# UC-520.net
KiCad netlist of a schematic drawn in Altium Designer
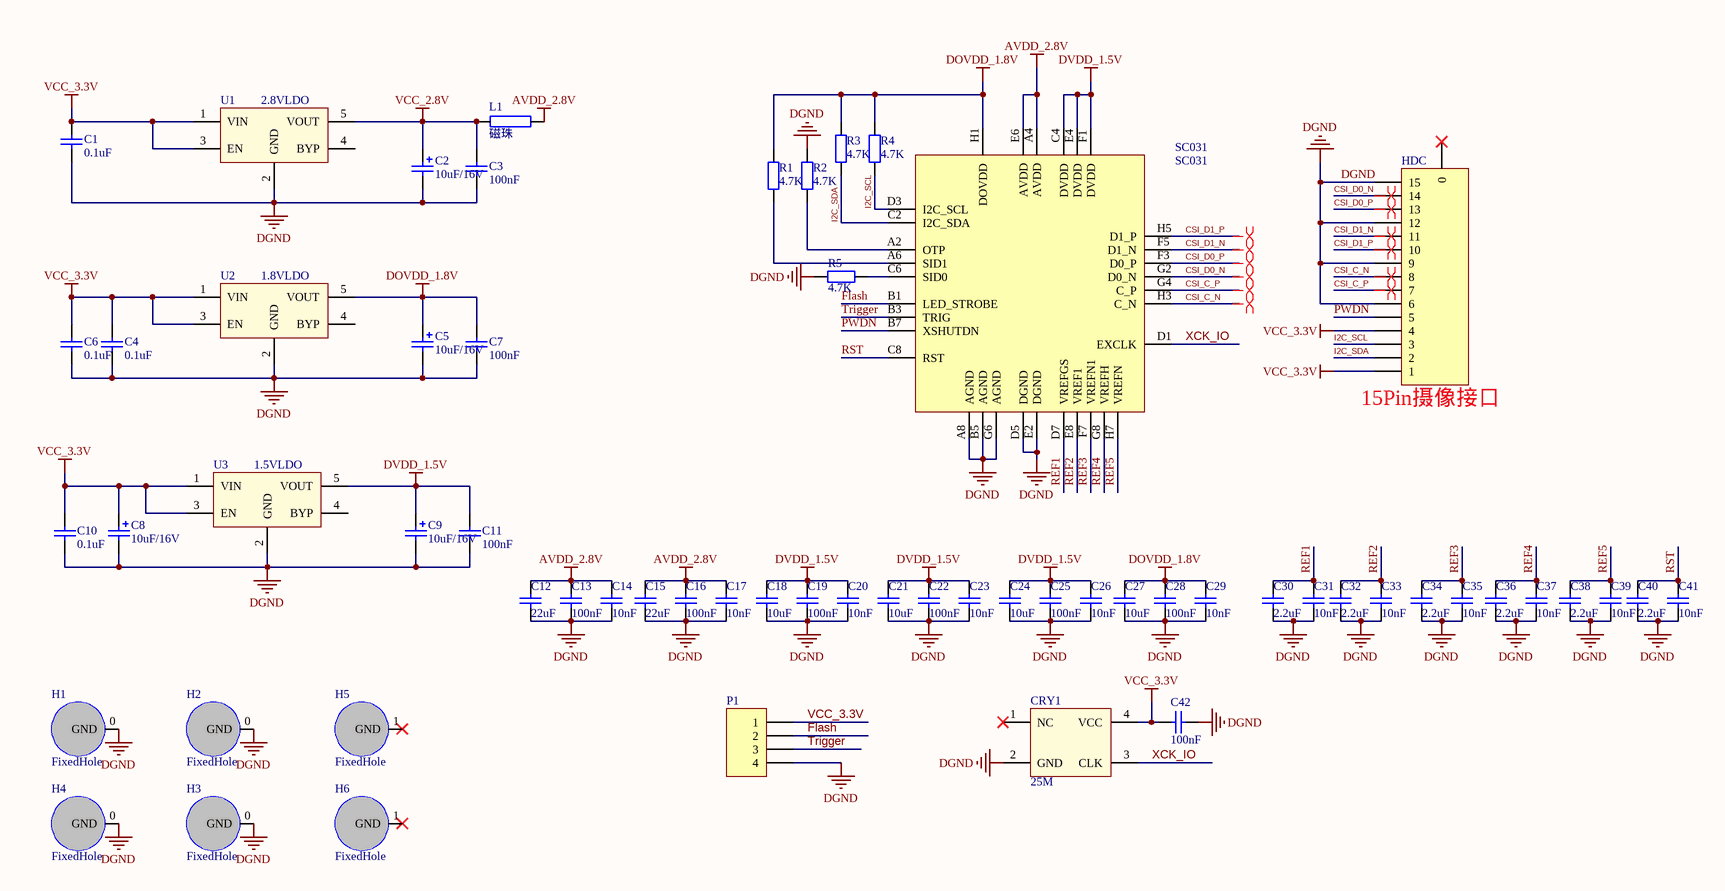
[diagram p0: UC-520.SchDoc]

(export (version "E")
  (design (tool "Eeschema 10.0.6"))
  (components
    (comp (ref "C1")
      (value "0.1uF")
      (footprint "C0603")
      (description "Capacitor")
      (fields (field (name "PUBLISHER") "Altium Limited"))
      (libsource (lib "Miscellaneous Devices") (part "Cap"))
    )
    (comp (ref "C2")
      (value "10uF/16V")
      (footprint "钽电容（A型）")
      (description "Polarized Capacitor (Axial)")
      (fields (field (name "PUBLISHER") "Altium Limited"))
      (libsource (lib "Miscellaneous Devices") (part "Cap Pol2"))
    )
    (comp (ref "C3")
      (value "100nF")
      (footprint "C0603")
      (description "Capacitor")
      (fields (field (name "PUBLISHER") "Altium Limited"))
      (libsource (lib "Miscellaneous Devices") (part "Cap"))
    )
    (comp (ref "C4")
      (value "0.1uF")
      (footprint "C0603")
      (description "Capacitor")
      (fields (field (name "PUBLISHER") "Altium Limited"))
      (libsource (lib "Miscellaneous Devices") (part "Cap"))
    )
    (comp (ref "C5")
      (value "10uF/16V")
      (footprint "钽电容（A型）")
      (description "Polarized Capacitor (Axial)")
      (fields (field (name "PUBLISHER") "Altium Limited"))
      (libsource (lib "Miscellaneous Devices") (part "Cap Pol2"))
    )
    (comp (ref "C6")
      (value "0.1uF")
      (footprint "C0603")
      (description "Capacitor")
      (fields (field (name "PUBLISHER") "Altium Limited"))
      (libsource (lib "Miscellaneous Devices") (part "Cap"))
    )
    (comp (ref "C7")
      (value "100nF")
      (footprint "C0603")
      (description "Capacitor")
      (fields (field (name "PUBLISHER") "Altium Limited"))
      (libsource (lib "Miscellaneous Devices") (part "Cap"))
    )
    (comp (ref "C8")
      (value "10uF/16V")
      (footprint "钽电容（A型）")
      (description "Polarized Capacitor (Axial)")
      (fields (field (name "PUBLISHER") "Altium Limited"))
      (libsource (lib "Miscellaneous Devices") (part "Cap Pol2"))
    )
    (comp (ref "C9")
      (value "10uF/16V")
      (footprint "钽电容（A型）")
      (description "Polarized Capacitor (Axial)")
      (fields (field (name "PUBLISHER") "Altium Limited"))
      (libsource (lib "Miscellaneous Devices") (part "Cap Pol2"))
    )
    (comp (ref "C10")
      (value "0.1uF")
      (footprint "C0603")
      (description "Capacitor")
      (fields (field (name "PUBLISHER") "Altium Limited"))
      (libsource (lib "Miscellaneous Devices") (part "Cap"))
    )
    (comp (ref "C11")
      (value "100nF")
      (footprint "C0603")
      (description "Capacitor")
      (fields (field (name "PUBLISHER") "Altium Limited"))
      (libsource (lib "Miscellaneous Devices") (part "Cap"))
    )
    (comp (ref "C12")
      (value "22uF")
      (footprint "C0603")
      (description "Capacitor")
      (fields (field (name "PUBLISHER") "Altium Limited"))
      (libsource (lib "Miscellaneous Devices") (part "Cap"))
    )
    (comp (ref "C13")
      (value "100nF")
      (footprint "C0603")
      (description "Capacitor")
      (fields (field (name "PUBLISHER") "Altium Limited"))
      (libsource (lib "Miscellaneous Devices") (part "Cap"))
    )
    (comp (ref "C14")
      (value "10nF")
      (footprint "C0603")
      (description "Capacitor")
      (fields (field (name "PUBLISHER") "Altium Limited"))
      (libsource (lib "Miscellaneous Devices") (part "Cap"))
    )
    (comp (ref "C15")
      (value "22uF")
      (footprint "C0603")
      (description "Capacitor")
      (fields (field (name "PUBLISHER") "Altium Limited"))
      (libsource (lib "Miscellaneous Devices") (part "Cap"))
    )
    (comp (ref "C16")
      (value "100nF")
      (footprint "C0603")
      (description "Capacitor")
      (fields (field (name "PUBLISHER") "Altium Limited"))
      (libsource (lib "Miscellaneous Devices") (part "Cap"))
    )
    (comp (ref "C17")
      (value "10nF")
      (footprint "C0603")
      (description "Capacitor")
      (fields (field (name "PUBLISHER") "Altium Limited"))
      (libsource (lib "Miscellaneous Devices") (part "Cap"))
    )
    (comp (ref "C18")
      (value "10uF")
      (footprint "C0603")
      (description "Capacitor")
      (fields (field (name "PUBLISHER") "Altium Limited"))
      (libsource (lib "Miscellaneous Devices") (part "Cap"))
    )
    (comp (ref "C19")
      (value "100nF")
      (footprint "C0603")
      (description "Capacitor")
      (fields (field (name "PUBLISHER") "Altium Limited"))
      (libsource (lib "Miscellaneous Devices") (part "Cap"))
    )
    (comp (ref "C20")
      (value "10nF")
      (footprint "C0603")
      (description "Capacitor")
      (fields (field (name "PUBLISHER") "Altium Limited"))
      (libsource (lib "Miscellaneous Devices") (part "Cap"))
    )
    (comp (ref "C21")
      (value "10uF")
      (footprint "C0603")
      (description "Capacitor")
      (fields (field (name "PUBLISHER") "Altium Limited"))
      (libsource (lib "Miscellaneous Devices") (part "Cap"))
    )
    (comp (ref "C22")
      (value "100nF")
      (footprint "C0603")
      (description "Capacitor")
      (fields (field (name "PUBLISHER") "Altium Limited"))
      (libsource (lib "Miscellaneous Devices") (part "Cap"))
    )
    (comp (ref "C23")
      (value "10nF")
      (footprint "C0603")
      (description "Capacitor")
      (fields (field (name "PUBLISHER") "Altium Limited"))
      (libsource (lib "Miscellaneous Devices") (part "Cap"))
    )
    (comp (ref "C24")
      (value "10uF")
      (footprint "C0603")
      (description "Capacitor")
      (fields (field (name "PUBLISHER") "Altium Limited"))
      (libsource (lib "Miscellaneous Devices") (part "Cap"))
    )
    (comp (ref "C25")
      (value "100nF")
      (footprint "C0603")
      (description "Capacitor")
      (fields (field (name "PUBLISHER") "Altium Limited"))
      (libsource (lib "Miscellaneous Devices") (part "Cap"))
    )
    (comp (ref "C26")
      (value "10nF")
      (footprint "C0603")
      (description "Capacitor")
      (fields (field (name "PUBLISHER") "Altium Limited"))
      (libsource (lib "Miscellaneous Devices") (part "Cap"))
    )
    (comp (ref "C27")
      (value "10uF")
      (footprint "C0603")
      (description "Capacitor")
      (fields (field (name "PUBLISHER") "Altium Limited"))
      (libsource (lib "Miscellaneous Devices") (part "Cap"))
    )
    (comp (ref "C28")
      (value "100nF")
      (footprint "C0603")
      (description "Capacitor")
      (fields (field (name "PUBLISHER") "Altium Limited"))
      (libsource (lib "Miscellaneous Devices") (part "Cap"))
    )
    (comp (ref "C29")
      (value "10nF")
      (footprint "C0603")
      (description "Capacitor")
      (fields (field (name "PUBLISHER") "Altium Limited"))
      (libsource (lib "Miscellaneous Devices") (part "Cap"))
    )
    (comp (ref "C30")
      (value "2.2uF")
      (footprint "C0603")
      (description "Capacitor")
      (fields (field (name "PUBLISHER") "Altium Limited"))
      (libsource (lib "Miscellaneous Devices") (part "Cap"))
    )
    (comp (ref "C31")
      (value "10nF")
      (footprint "C0603")
      (description "Capacitor")
      (fields (field (name "PUBLISHER") "Altium Limited"))
      (libsource (lib "Miscellaneous Devices") (part "Cap"))
    )
    (comp (ref "C32")
      (value "2.2uF")
      (footprint "C0603")
      (description "Capacitor")
      (fields (field (name "PUBLISHER") "Altium Limited"))
      (libsource (lib "Miscellaneous Devices") (part "Cap"))
    )
    (comp (ref "C33")
      (value "10nF")
      (footprint "C0603")
      (description "Capacitor")
      (fields (field (name "PUBLISHER") "Altium Limited"))
      (libsource (lib "Miscellaneous Devices") (part "Cap"))
    )
    (comp (ref "C34")
      (value "2.2uF")
      (footprint "C0603")
      (description "Capacitor")
      (fields (field (name "PUBLISHER") "Altium Limited"))
      (libsource (lib "Miscellaneous Devices") (part "Cap"))
    )
    (comp (ref "C35")
      (value "10nF")
      (footprint "C0603")
      (description "Capacitor")
      (fields (field (name "PUBLISHER") "Altium Limited"))
      (libsource (lib "Miscellaneous Devices") (part "Cap"))
    )
    (comp (ref "C36")
      (value "2.2uF")
      (footprint "C0603")
      (description "Capacitor")
      (fields (field (name "PUBLISHER") "Altium Limited"))
      (libsource (lib "Miscellaneous Devices") (part "Cap"))
    )
    (comp (ref "C37")
      (value "10nF")
      (footprint "C0603")
      (description "Capacitor")
      (fields (field (name "PUBLISHER") "Altium Limited"))
      (libsource (lib "Miscellaneous Devices") (part "Cap"))
    )
    (comp (ref "C38")
      (value "2.2uF")
      (footprint "C0603")
      (description "Capacitor")
      (fields (field (name "PUBLISHER") "Altium Limited"))
      (libsource (lib "Miscellaneous Devices") (part "Cap"))
    )
    (comp (ref "C39")
      (value "10nF")
      (footprint "C0603")
      (description "Capacitor")
      (fields (field (name "PUBLISHER") "Altium Limited"))
      (libsource (lib "Miscellaneous Devices") (part "Cap"))
    )
    (comp (ref "C40")
      (value "2.2uF")
      (footprint "C0603")
      (description "Capacitor")
      (fields (field (name "PUBLISHER") "Altium Limited"))
      (libsource (lib "Miscellaneous Devices") (part "Cap"))
    )
    (comp (ref "C41")
      (value "10nF")
      (footprint "C0603")
      (description "Capacitor")
      (fields (field (name "PUBLISHER") "Altium Limited"))
      (libsource (lib "Miscellaneous Devices") (part "Cap"))
    )
    (comp (ref "C42")
      (value "100nF")
      (footprint "C0603")
      (description "Capacitor")
      (fields (field (name "PUBLISHER") "Altium Limited"))
      (libsource (lib "Miscellaneous Devices") (part "Cap"))
    )
    (comp (ref "CRY1")
      (value "25M")
      (footprint "爱普生晶振3.2×2.5MM")
      (libsource (lib "MT9F002_V2.0") (part "24M"))
    )
    (comp (ref "H1")
      (value "FixedHole")
      (footprint "HOLE_M2")
      (libsource (lib "ITMS-02调试电缆转接板") (part "固定孔"))
    )
    (comp (ref "H2")
      (value "FixedHole")
      (footprint "HOLE_M2")
      (libsource (lib "ITMS-02调试电缆转接板") (part "固定孔"))
    )
    (comp (ref "H3")
      (value "FixedHole")
      (footprint "HOLE_M2")
      (libsource (lib "ITMS-02调试电缆转接板") (part "固定孔"))
    )
    (comp (ref "H4")
      (value "FixedHole")
      (footprint "HOLE_M2")
      (libsource (lib "ITMS-02调试电缆转接板") (part "固定孔"))
    )
    (comp (ref "H5") (value "FixedHole") (footprint "HOLE_M2") (libsource (lib "") (part "固定孔_1")))
    (comp (ref "H6") (value "FixedHole") (footprint "HOLE_M2") (libsource (lib "") (part "固定孔_1")))
    (comp (ref "HDC")
      (value "Header 15")
      (footprint "OV5647_MIPI")
      (description "Header, 15-Pin")
      (fields (field (name "PUBLISHER") "Altium Limited"))
      (libsource (lib "摄像头转换板_OV5647_MIPI V1.0") (part "Header 15"))
    )
    (comp (ref "L1") (value "磁珠") (footprint "L0603") (libsource (lib "*") (part "RES")))
    (comp (ref "P1")
      (value "Header 4")
      (footprint "HDR1X4")
      (description "Header, 4-Pin")
      (fields (field (name "PUBLISHER") "Altium Limited"))
      (libsource (lib "Miscellaneous Connectors") (part "Header 4"))
    )
    (comp (ref "R1")
      (value "4.7K")
      (footprint "R0603")
      (description "Resistor")
      (fields (field (name "PUBLISHER") "Altium Limited"))
      (libsource (lib "") (part "Res2_2"))
    )
    (comp (ref "R2")
      (value "4.7K")
      (footprint "R0603")
      (description "Resistor")
      (fields (field (name "PUBLISHER") "Altium Limited"))
      (libsource (lib "Miscellaneous Devices") (part "Res2"))
    )
    (comp (ref "R3")
      (value "4.7K")
      (footprint "R0603")
      (description "Resistor")
      (fields (field (name "PUBLISHER") "Altium Limited"))
      (libsource (lib "Miscellaneous Devices") (part "Res2"))
    )
    (comp (ref "R4")
      (value "4.7K")
      (footprint "R0603")
      (description "Resistor")
      (fields (field (name "PUBLISHER") "Altium Limited"))
      (libsource (lib "Miscellaneous Devices") (part "Res2"))
    )
    (comp (ref "R5")
      (value "4.7K")
      (footprint "R0603")
      (description "Resistor")
      (fields (field (name "PUBLISHER") "Altium Limited"))
      (libsource (lib "") (part "Res2_1"))
    )
    (comp (ref "SC031") (value "SC031") (footprint "BGA32") (libsource (lib "SC031") (part "SC031")))
    (comp (ref "U1")
      (value "2.8VLDO")
      (footprint "SOT23-5")
      (libsource (lib "MT9F002_V2.0") (part "2.8VLDO"))
    )
    (comp (ref "U2")
      (value "1.8VLDO")
      (footprint "SOT23-5")
      (libsource (lib "MT9F002_V2.0") (part "2.8VLDO"))
    )
    (comp (ref "U3")
      (value "1.5VLDO")
      (footprint "SOT23-5")
      (libsource (lib "MT9F002_V2.0") (part "2.8VLDO"))
    )
  )
  (nets
    (net (code "1") (name "/CSI_C_N") (class "Default")
      (node (ref "HDC") (pin "8") (pinfunction "8_8") (pintype "passive"))
      (node (ref "SC031") (pin "H3") (pinfunction "C_N_H3") (pintype "passive"))
    )
    (net (code "2") (name "/CSI_C_P") (class "Default")
      (node (ref "HDC") (pin "7") (pinfunction "7_7") (pintype "passive"))
      (node (ref "SC031") (pin "G4") (pinfunction "C_P_G4") (pintype "passive"))
    )
    (net (code "3") (name "/CSI_D0_N") (class "Default")
      (node (ref "HDC") (pin "14") (pinfunction "14_14") (pintype "passive"))
      (node (ref "SC031") (pin "G2") (pinfunction "D0_N_G2") (pintype "passive"))
    )
    (net (code "4") (name "/CSI_D0_P") (class "Default")
      (node (ref "HDC") (pin "13") (pinfunction "13_13") (pintype "passive"))
      (node (ref "SC031") (pin "F3") (pinfunction "D0_P_F3") (pintype "passive"))
    )
    (net (code "5") (name "/CSI_D1_N") (class "Default")
      (node (ref "HDC") (pin "11") (pinfunction "11_11") (pintype "passive"))
      (node (ref "SC031") (pin "F5") (pinfunction "D1_N_F5") (pintype "passive"))
    )
    (net (code "6") (name "/CSI_D1_P") (class "Default")
      (node (ref "HDC") (pin "10") (pinfunction "10_10") (pintype "passive"))
      (node (ref "SC031") (pin "H5") (pinfunction "D1_P_H5") (pintype "passive"))
    )
    (net (code "7") (name "/Flash") (class "Default")
      (node (ref "P1") (pin "2") (pinfunction "2_2") (pintype "passive"))
      (node (ref "SC031") (pin "B1") (pinfunction "LED_STROBE_B1") (pintype "passive"))
    )
    (net (code "8") (name "/I2C_SCL") (class "Default")
      (node (ref "HDC") (pin "3") (pinfunction "3_3") (pintype "passive"))
      (node (ref "R4") (pin "1") (pinfunction "1_1") (pintype "passive"))
      (node (ref "SC031") (pin "D3") (pinfunction "I2C_SCL_D3") (pintype "passive"))
    )
    (net (code "9") (name "/I2C_SDA") (class "Default")
      (node (ref "HDC") (pin "2") (pinfunction "2_2") (pintype "passive"))
      (node (ref "R3") (pin "1") (pinfunction "1_1") (pintype "passive"))
      (node (ref "SC031") (pin "C2") (pinfunction "I2C_SDA_C2") (pintype "passive"))
    )
    (net (code "10") (name "/PWDN") (class "Default")
      (node (ref "HDC") (pin "5") (pinfunction "5_5") (pintype "passive"))
      (node (ref "SC031") (pin "B7") (pinfunction "XSHUTDN_B7") (pintype "passive"))
    )
    (net (code "11") (name "/REF1") (class "Default")
      (node (ref "C30") (pin "2") (pinfunction "2_2") (pintype "passive"))
      (node (ref "C31") (pin "2") (pinfunction "2_2") (pintype "passive"))
      (node (ref "SC031") (pin "D7") (pinfunction "VREFGS_D7") (pintype "passive"))
    )
    (net (code "12") (name "/REF2") (class "Default")
      (node (ref "C32") (pin "2") (pinfunction "2_2") (pintype "passive"))
      (node (ref "C33") (pin "2") (pinfunction "2_2") (pintype "passive"))
      (node (ref "SC031") (pin "E8") (pinfunction "VREF1_E8") (pintype "passive"))
    )
    (net (code "13") (name "/REF3") (class "Default")
      (node (ref "C34") (pin "2") (pinfunction "2_2") (pintype "passive"))
      (node (ref "C35") (pin "2") (pinfunction "2_2") (pintype "passive"))
      (node (ref "SC031") (pin "F7") (pinfunction "VREFN1_F7") (pintype "passive"))
    )
    (net (code "14") (name "/REF4") (class "Default")
      (node (ref "C36") (pin "2") (pinfunction "2_2") (pintype "passive"))
      (node (ref "C37") (pin "2") (pinfunction "2_2") (pintype "passive"))
      (node (ref "SC031") (pin "G8") (pinfunction "VREFH_G8") (pintype "passive"))
    )
    (net (code "15") (name "/REF5") (class "Default")
      (node (ref "C38") (pin "2") (pinfunction "2_2") (pintype "passive"))
      (node (ref "C39") (pin "2") (pinfunction "2_2") (pintype "passive"))
      (node (ref "SC031") (pin "H7") (pinfunction "VREFN_H7") (pintype "passive"))
    )
    (net (code "16") (name "/RST") (class "Default")
      (node (ref "C40") (pin "2") (pinfunction "2_2") (pintype "passive"))
      (node (ref "C41") (pin "2") (pinfunction "2_2") (pintype "passive"))
      (node (ref "SC031") (pin "C8") (pinfunction "RST_C8") (pintype "passive"))
    )
    (net (code "17") (name "/Trigger") (class "Default")
      (node (ref "P1") (pin "3") (pinfunction "3_3") (pintype "passive"))
      (node (ref "SC031") (pin "B3") (pinfunction "TRIG_B3") (pintype "passive"))
    )
    (net (code "18") (name "/XCK_IO") (class "Default")
      (node (ref "CRY1") (pin "3") (pinfunction "CLK_3") (pintype "passive"))
      (node (ref "SC031") (pin "D1") (pinfunction "EXCLK_D1") (pintype "passive"))
    )
    (net (code "19") (name "AVDD_2.8V") (class "Default")
      (node (ref "C12") (pin "2") (pinfunction "2_2") (pintype "passive"))
      (node (ref "C13") (pin "2") (pinfunction "2_2") (pintype "passive"))
      (node (ref "C14") (pin "2") (pinfunction "2_2") (pintype "passive"))
      (node (ref "C15") (pin "2") (pinfunction "2_2") (pintype "passive"))
      (node (ref "C16") (pin "2") (pinfunction "2_2") (pintype "passive"))
      (node (ref "C17") (pin "2") (pinfunction "2_2") (pintype "passive"))
      (node (ref "L1") (pin "1") (pinfunction "1_1") (pintype "passive"))
      (node (ref "SC031") (pin "A4") (pinfunction "AVDD_A4") (pintype "passive"))
      (node (ref "SC031") (pin "E6") (pinfunction "AVDD_E6") (pintype "passive"))
    )
    (net (code "20") (name "DGND") (class "Default")
      (node (ref "C1") (pin "2") (pinfunction "2_2") (pintype "passive"))
      (node (ref "C10") (pin "2") (pinfunction "2_2") (pintype "passive"))
      (node (ref "C11") (pin "2") (pinfunction "2_2") (pintype "passive"))
      (node (ref "C12") (pin "1") (pinfunction "1_1") (pintype "passive"))
      (node (ref "C13") (pin "1") (pinfunction "1_1") (pintype "passive"))
      (node (ref "C14") (pin "1") (pinfunction "1_1") (pintype "passive"))
      (node (ref "C15") (pin "1") (pinfunction "1_1") (pintype "passive"))
      (node (ref "C16") (pin "1") (pinfunction "1_1") (pintype "passive"))
      (node (ref "C17") (pin "1") (pinfunction "1_1") (pintype "passive"))
      (node (ref "C18") (pin "1") (pinfunction "1_1") (pintype "passive"))
      (node (ref "C19") (pin "1") (pinfunction "1_1") (pintype "passive"))
      (node (ref "C2") (pin "2") (pinfunction "2_2") (pintype "passive"))
      (node (ref "C20") (pin "1") (pinfunction "1_1") (pintype "passive"))
      (node (ref "C21") (pin "1") (pinfunction "1_1") (pintype "passive"))
      (node (ref "C22") (pin "1") (pinfunction "1_1") (pintype "passive"))
      (node (ref "C23") (pin "1") (pinfunction "1_1") (pintype "passive"))
      (node (ref "C24") (pin "1") (pinfunction "1_1") (pintype "passive"))
      (node (ref "C25") (pin "1") (pinfunction "1_1") (pintype "passive"))
      (node (ref "C26") (pin "1") (pinfunction "1_1") (pintype "passive"))
      (node (ref "C27") (pin "1") (pinfunction "1_1") (pintype "passive"))
      (node (ref "C28") (pin "1") (pinfunction "1_1") (pintype "passive"))
      (node (ref "C29") (pin "1") (pinfunction "1_1") (pintype "passive"))
      (node (ref "C3") (pin "2") (pinfunction "2_2") (pintype "passive"))
      (node (ref "C30") (pin "1") (pinfunction "1_1") (pintype "passive"))
      (node (ref "C31") (pin "1") (pinfunction "1_1") (pintype "passive"))
      (node (ref "C32") (pin "1") (pinfunction "1_1") (pintype "passive"))
      (node (ref "C33") (pin "1") (pinfunction "1_1") (pintype "passive"))
      (node (ref "C34") (pin "1") (pinfunction "1_1") (pintype "passive"))
      (node (ref "C35") (pin "1") (pinfunction "1_1") (pintype "passive"))
      (node (ref "C36") (pin "1") (pinfunction "1_1") (pintype "passive"))
      (node (ref "C37") (pin "1") (pinfunction "1_1") (pintype "passive"))
      (node (ref "C38") (pin "1") (pinfunction "1_1") (pintype "passive"))
      (node (ref "C39") (pin "1") (pinfunction "1_1") (pintype "passive"))
      (node (ref "C4") (pin "2") (pinfunction "2_2") (pintype "passive"))
      (node (ref "C40") (pin "1") (pinfunction "1_1") (pintype "passive"))
      (node (ref "C41") (pin "1") (pinfunction "1_1") (pintype "passive"))
      (node (ref "C42") (pin "1") (pinfunction "1_1") (pintype "passive"))
      (node (ref "C5") (pin "2") (pinfunction "2_2") (pintype "passive"))
      (node (ref "C6") (pin "2") (pinfunction "2_2") (pintype "passive"))
      (node (ref "C7") (pin "2") (pinfunction "2_2") (pintype "passive"))
      (node (ref "C8") (pin "2") (pinfunction "2_2") (pintype "passive"))
      (node (ref "C9") (pin "2") (pinfunction "2_2") (pintype "passive"))
      (node (ref "CRY1") (pin "2") (pinfunction "GND_2") (pintype "passive"))
      (node (ref "H1") (pin "0") (pinfunction "GND_0") (pintype "passive"))
      (node (ref "H2") (pin "0") (pinfunction "GND_0") (pintype "passive"))
      (node (ref "H3") (pin "0") (pinfunction "GND_0") (pintype "passive"))
      (node (ref "H4") (pin "0") (pinfunction "GND_0") (pintype "passive"))
      (node (ref "HDC") (pin "12") (pinfunction "12_12") (pintype "passive"))
      (node (ref "HDC") (pin "15") (pinfunction "15_15") (pintype "passive"))
      (node (ref "HDC") (pin "6") (pinfunction "6_6") (pintype "passive"))
      (node (ref "HDC") (pin "9") (pinfunction "9_9") (pintype "passive"))
      (node (ref "P1") (pin "4") (pinfunction "4_4") (pintype "passive"))
      (node (ref "R2") (pin "2") (pinfunction "2_2") (pintype "passive"))
      (node (ref "R5") (pin "2") (pinfunction "2_2") (pintype "passive"))
      (node (ref "SC031") (pin "A8") (pinfunction "AGND_A8") (pintype "passive"))
      (node (ref "SC031") (pin "B5") (pinfunction "AGND_B5") (pintype "passive"))
      (node (ref "SC031") (pin "D5") (pinfunction "DGND_D5") (pintype "passive"))
      (node (ref "SC031") (pin "E2") (pinfunction "DGND_E2") (pintype "passive"))
      (node (ref "SC031") (pin "G6") (pinfunction "AGND_G6") (pintype "passive"))
      (node (ref "U1") (pin "2") (pinfunction "GND_2") (pintype "passive"))
      (node (ref "U2") (pin "2") (pinfunction "GND_2") (pintype "passive"))
      (node (ref "U3") (pin "2") (pinfunction "GND_2") (pintype "passive"))
    )
    (net (code "21") (name "DOVDD_1.8V") (class "Default")
      (node (ref "C27") (pin "2") (pinfunction "2_2") (pintype "passive"))
      (node (ref "C28") (pin "2") (pinfunction "2_2") (pintype "passive"))
      (node (ref "C29") (pin "2") (pinfunction "2_2") (pintype "passive"))
      (node (ref "C5") (pin "1") (pinfunction "1_1") (pintype "passive"))
      (node (ref "C7") (pin "1") (pinfunction "1_1") (pintype "passive"))
      (node (ref "R1") (pin "1") (pinfunction "1_1") (pintype "passive"))
      (node (ref "R3") (pin "2") (pinfunction "2_2") (pintype "passive"))
      (node (ref "R4") (pin "2") (pinfunction "2_2") (pintype "passive"))
      (node (ref "SC031") (pin "H1") (pinfunction "DOVDD_H1") (pintype "passive"))
      (node (ref "U2") (pin "5") (pinfunction "VOUT_5") (pintype "passive"))
    )
    (net (code "22") (name "DVDD_1.5V") (class "Default")
      (node (ref "C11") (pin "1") (pinfunction "1_1") (pintype "passive"))
      (node (ref "C18") (pin "2") (pinfunction "2_2") (pintype "passive"))
      (node (ref "C19") (pin "2") (pinfunction "2_2") (pintype "passive"))
      (node (ref "C20") (pin "2") (pinfunction "2_2") (pintype "passive"))
      (node (ref "C21") (pin "2") (pinfunction "2_2") (pintype "passive"))
      (node (ref "C22") (pin "2") (pinfunction "2_2") (pintype "passive"))
      (node (ref "C23") (pin "2") (pinfunction "2_2") (pintype "passive"))
      (node (ref "C24") (pin "2") (pinfunction "2_2") (pintype "passive"))
      (node (ref "C25") (pin "2") (pinfunction "2_2") (pintype "passive"))
      (node (ref "C26") (pin "2") (pinfunction "2_2") (pintype "passive"))
      (node (ref "C9") (pin "1") (pinfunction "1_1") (pintype "passive"))
      (node (ref "SC031") (pin "C4") (pinfunction "DVDD_C4") (pintype "passive"))
      (node (ref "SC031") (pin "E4") (pinfunction "DVDD_E4") (pintype "passive"))
      (node (ref "SC031") (pin "F1") (pinfunction "DVDD_F1") (pintype "passive"))
      (node (ref "U3") (pin "5") (pinfunction "VOUT_5") (pintype "passive"))
    )
    (net (code "23") (name "Net-(SC031-OTP)") (class "Default")
      (node (ref "R2") (pin "1") (pinfunction "1_1") (pintype "passive"))
      (node (ref "SC031") (pin "A2") (pinfunction "OTP_A2") (pintype "passive"))
    )
    (net (code "24") (name "Net-(SC031-SID0)") (class "Default")
      (node (ref "R5") (pin "1") (pinfunction "1_1") (pintype "passive"))
      (node (ref "SC031") (pin "C6") (pinfunction "SID0_C6") (pintype "passive"))
    )
    (net (code "25") (name "Net-(SC031-SID1)") (class "Default")
      (node (ref "R1") (pin "2") (pinfunction "2_2") (pintype "passive"))
      (node (ref "SC031") (pin "A6") (pinfunction "SID1_A6") (pintype "passive"))
    )
    (net (code "26") (name "VCC_2.8V") (class "Default")
      (node (ref "C2") (pin "1") (pinfunction "1_1") (pintype "passive"))
      (node (ref "C3") (pin "1") (pinfunction "1_1") (pintype "passive"))
      (node (ref "L1") (pin "2") (pinfunction "2_2") (pintype "passive"))
      (node (ref "U1") (pin "5") (pinfunction "VOUT_5") (pintype "passive"))
    )
    (net (code "27") (name "VCC_3.3V") (class "Default")
      (node (ref "C1") (pin "1") (pinfunction "1_1") (pintype "passive"))
      (node (ref "C10") (pin "1") (pinfunction "1_1") (pintype "passive"))
      (node (ref "C4") (pin "1") (pinfunction "1_1") (pintype "passive"))
      (node (ref "C42") (pin "2") (pinfunction "2_2") (pintype "passive"))
      (node (ref "C6") (pin "1") (pinfunction "1_1") (pintype "passive"))
      (node (ref "C8") (pin "1") (pinfunction "1_1") (pintype "passive"))
      (node (ref "CRY1") (pin "4") (pinfunction "VCC_4") (pintype "passive"))
      (node (ref "HDC") (pin "1") (pinfunction "1_1") (pintype "passive"))
      (node (ref "HDC") (pin "4") (pinfunction "4_4") (pintype "passive"))
      (node (ref "P1") (pin "1") (pinfunction "1_1") (pintype "passive"))
      (node (ref "U1") (pin "1") (pinfunction "VIN_1") (pintype "passive"))
      (node (ref "U1") (pin "3") (pinfunction "EN_3") (pintype "passive"))
      (node (ref "U2") (pin "1") (pinfunction "VIN_1") (pintype "passive"))
      (node (ref "U2") (pin "3") (pinfunction "EN_3") (pintype "passive"))
      (node (ref "U3") (pin "1") (pinfunction "VIN_1") (pintype "passive"))
      (node (ref "U3") (pin "3") (pinfunction "EN_3") (pintype "passive"))
    )
    (net (code "28") (name "unconnected-(CRY1-NC-Pad1)") (class "Default")
      (node (ref "CRY1") (pin "1") (pinfunction "NC_1") (pintype "passive+no_connect"))
    )
    (net (code "29") (name "unconnected-(H5-GND-Pad1)") (class "Default")
      (node (ref "H5") (pin "1") (pinfunction "GND_1") (pintype "passive+no_connect"))
    )
    (net (code "30") (name "unconnected-(H6-GND-Pad1)") (class "Default")
      (node (ref "H6") (pin "1") (pinfunction "GND_1") (pintype "passive+no_connect"))
    )
    (net (code "31") (name "unconnected-(HDC-Pad0)") (class "Default")
      (node (ref "HDC") (pin "0") (pinfunction "0_0") (pintype "passive+no_connect"))
    )
    (net (code "32") (name "unconnected-(U1-BYP-Pad4)") (class "Default")
      (node (ref "U1") (pin "4") (pinfunction "BYP_4") (pintype "passive"))
    )
    (net (code "33") (name "unconnected-(U2-BYP-Pad4)") (class "Default")
      (node (ref "U2") (pin "4") (pinfunction "BYP_4") (pintype "passive"))
    )
    (net (code "34") (name "unconnected-(U3-BYP-Pad4)") (class "Default")
      (node (ref "U3") (pin "4") (pinfunction "BYP_4") (pintype "passive"))
    )
  )
)
